# Isolated_gate_drive.net
KiCad netlist of a schematic drawn in Altium Designer
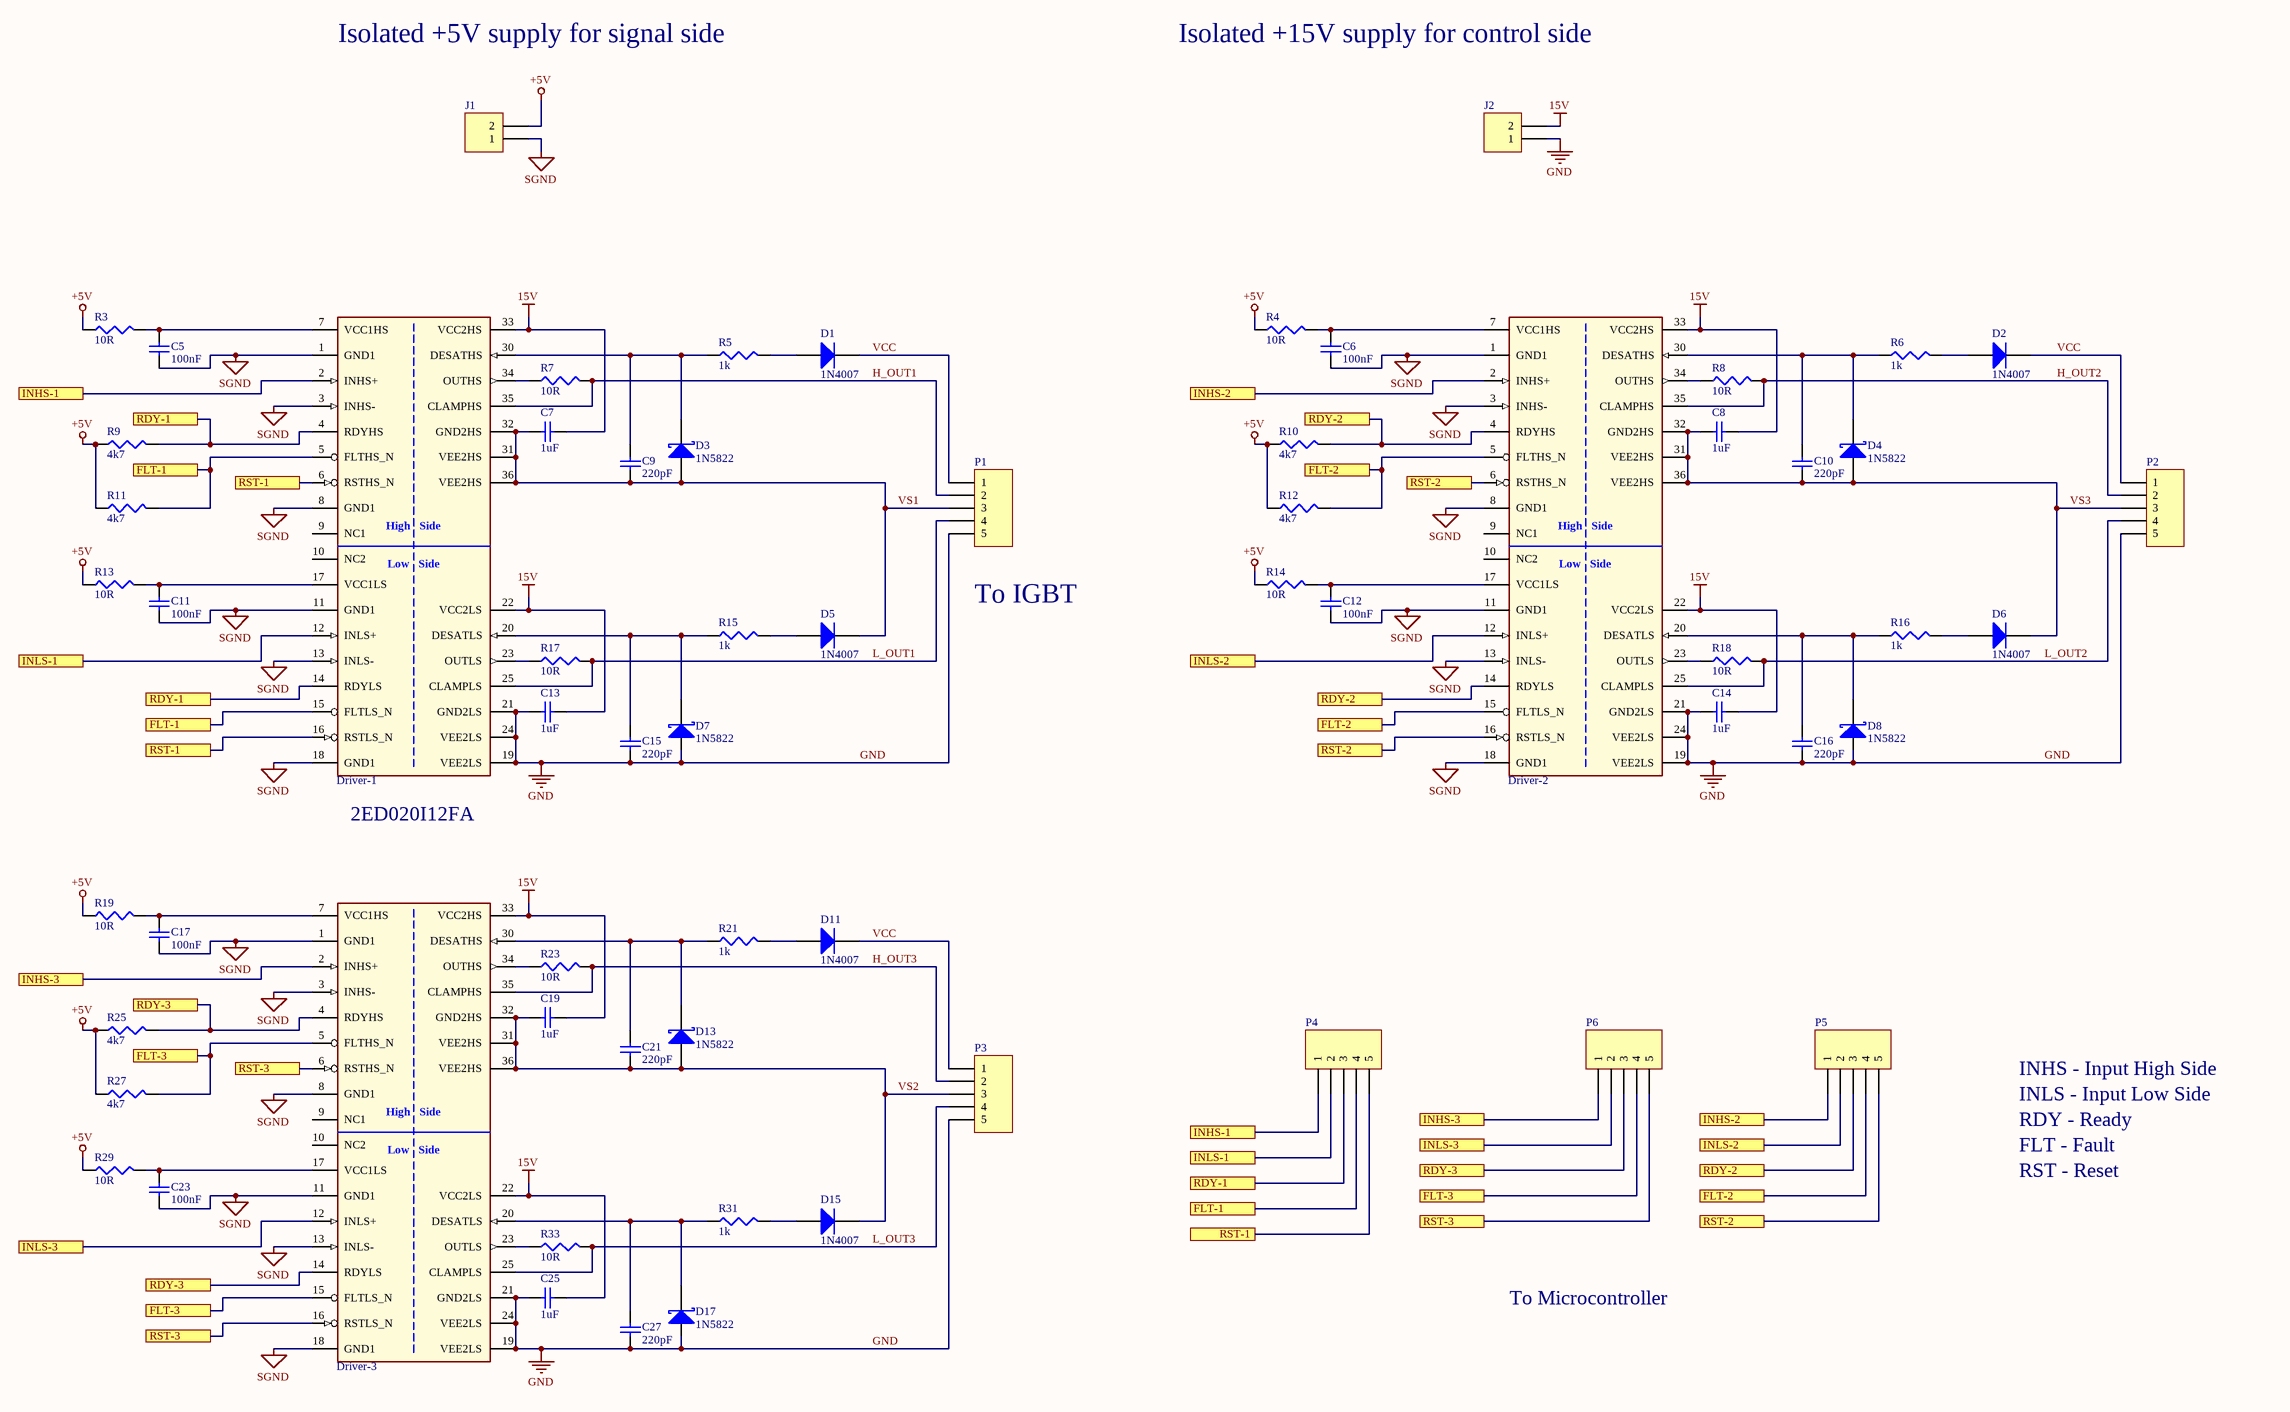
[diagram p0: Isolated_gate_drive.SchDoc]

(export (version "E")
  (design (tool "Eeschema 10.0.6"))
  (components
    (comp (ref "C5")
      (value "100nF")
      (footprint "C0805")
      (description "Capacitor")
      (fields (field (name "Comment") "Cap") (field (name "PUBLISHER") "Altium Limited"))
      (libsource (lib "Miscellaneous Devices") (part "Cap"))
    )
    (comp (ref "C6")
      (value "100nF")
      (footprint "C0805")
      (description "Capacitor")
      (fields (field (name "Comment") "Cap") (field (name "PUBLISHER") "Altium Limited"))
      (libsource (lib "Miscellaneous Devices") (part "Cap"))
    )
    (comp (ref "C7")
      (value "1uF")
      (footprint "C0805")
      (description "Capacitor")
      (fields (field (name "Comment") "Cap") (field (name "PUBLISHER") "Altium Limited"))
      (libsource (lib "Miscellaneous Devices") (part "Cap"))
    )
    (comp (ref "C8")
      (value "1uF")
      (footprint "C0805")
      (description "Capacitor")
      (fields (field (name "Comment") "Cap") (field (name "PUBLISHER") "Altium Limited"))
      (libsource (lib "Miscellaneous Devices") (part "Cap"))
    )
    (comp (ref "C9")
      (value "220pF")
      (footprint "C0805")
      (description "Capacitor")
      (fields (field (name "Comment") "Cap") (field (name "PUBLISHER") "Altium Limited"))
      (libsource (lib "Miscellaneous Devices") (part "Cap"))
    )
    (comp (ref "C10")
      (value "220pF")
      (footprint "C0805")
      (description "Capacitor")
      (fields (field (name "Comment") "Cap") (field (name "PUBLISHER") "Altium Limited"))
      (libsource (lib "Miscellaneous Devices") (part "Cap"))
    )
    (comp (ref "C11")
      (value "100nF")
      (footprint "C0805")
      (description "Capacitor")
      (fields (field (name "Comment") "Cap") (field (name "PUBLISHER") "Altium Limited"))
      (libsource (lib "Miscellaneous Devices") (part "Cap"))
    )
    (comp (ref "C12")
      (value "100nF")
      (footprint "C0805")
      (description "Capacitor")
      (fields (field (name "Comment") "Cap") (field (name "PUBLISHER") "Altium Limited"))
      (libsource (lib "Miscellaneous Devices") (part "Cap"))
    )
    (comp (ref "C13")
      (value "1uF")
      (footprint "C0805")
      (description "Capacitor")
      (fields (field (name "Comment") "Cap") (field (name "PUBLISHER") "Altium Limited"))
      (libsource (lib "Miscellaneous Devices") (part "Cap"))
    )
    (comp (ref "C14")
      (value "1uF")
      (footprint "C0805")
      (description "Capacitor")
      (fields (field (name "Comment") "Cap") (field (name "PUBLISHER") "Altium Limited"))
      (libsource (lib "Miscellaneous Devices") (part "Cap"))
    )
    (comp (ref "C15")
      (value "220pF")
      (footprint "C0805")
      (description "Capacitor")
      (fields (field (name "Comment") "Cap") (field (name "PUBLISHER") "Altium Limited"))
      (libsource (lib "Miscellaneous Devices") (part "Cap"))
    )
    (comp (ref "C16")
      (value "220pF")
      (footprint "C0805")
      (description "Capacitor")
      (fields (field (name "Comment") "Cap") (field (name "PUBLISHER") "Altium Limited"))
      (libsource (lib "Miscellaneous Devices") (part "Cap"))
    )
    (comp (ref "C17")
      (value "100nF")
      (footprint "C0805")
      (description "Capacitor")
      (fields (field (name "Comment") "Cap") (field (name "PUBLISHER") "Altium Limited"))
      (libsource (lib "Miscellaneous Devices") (part "Cap"))
    )
    (comp (ref "C19")
      (value "1uF")
      (footprint "C0805")
      (description "Capacitor")
      (fields (field (name "Comment") "Cap") (field (name "PUBLISHER") "Altium Limited"))
      (libsource (lib "Miscellaneous Devices") (part "Cap"))
    )
    (comp (ref "C21")
      (value "220pF")
      (footprint "C0805")
      (description "Capacitor")
      (fields (field (name "Comment") "Cap") (field (name "PUBLISHER") "Altium Limited"))
      (libsource (lib "Miscellaneous Devices") (part "Cap"))
    )
    (comp (ref "C23")
      (value "100nF")
      (footprint "C0805")
      (description "Capacitor")
      (fields (field (name "Comment") "Cap") (field (name "PUBLISHER") "Altium Limited"))
      (libsource (lib "Miscellaneous Devices") (part "Cap"))
    )
    (comp (ref "C25")
      (value "1uF")
      (footprint "C0805")
      (description "Capacitor")
      (fields (field (name "Comment") "Cap") (field (name "PUBLISHER") "Altium Limited"))
      (libsource (lib "Miscellaneous Devices") (part "Cap"))
    )
    (comp (ref "C27")
      (value "220pF")
      (footprint "C0805")
      (description "Capacitor")
      (fields (field (name "Comment") "Cap") (field (name "PUBLISHER") "Altium Limited"))
      (libsource (lib "Miscellaneous Devices") (part "Cap"))
    )
    (comp (ref "D1")
      (value "1N4007")
      (footprint "M7 SMA")
      (description "Default Diode")
      (fields (field (name "PUBLISHER") "Altium Limited"))
      (libsource (lib "Miscellaneous Devices") (part "Diode"))
    )
    (comp (ref "D2")
      (value "1N4007")
      (footprint "M7 SMA")
      (description "Default Diode")
      (fields (field (name "PUBLISHER") "Altium Limited"))
      (libsource (lib "Miscellaneous Devices") (part "Diode"))
    )
    (comp (ref "D3")
      (value "1N5822")
      (footprint "SMB")
      (description "Schottky Diode")
      (fields (field (name "PUBLISHER") "Altium Limited"))
      (libsource (lib "Miscellaneous Devices") (part "D Schottky"))
    )
    (comp (ref "D4")
      (value "1N5822")
      (footprint "SMB")
      (description "Schottky Diode")
      (fields (field (name "PUBLISHER") "Altium Limited"))
      (libsource (lib "Miscellaneous Devices") (part "D Schottky"))
    )
    (comp (ref "D5")
      (value "1N4007")
      (footprint "M7 SMA")
      (description "Default Diode")
      (fields (field (name "PUBLISHER") "Altium Limited"))
      (libsource (lib "Miscellaneous Devices") (part "Diode"))
    )
    (comp (ref "D6")
      (value "1N4007")
      (footprint "M7 SMA")
      (description "Default Diode")
      (fields (field (name "PUBLISHER") "Altium Limited"))
      (libsource (lib "Miscellaneous Devices") (part "Diode"))
    )
    (comp (ref "D7")
      (value "1N5822")
      (footprint "SMB")
      (description "Schottky Diode")
      (fields (field (name "PUBLISHER") "Altium Limited"))
      (libsource (lib "Miscellaneous Devices") (part "D Schottky"))
    )
    (comp (ref "D8")
      (value "1N5822")
      (footprint "SMB")
      (description "Schottky Diode")
      (fields (field (name "PUBLISHER") "Altium Limited"))
      (libsource (lib "Miscellaneous Devices") (part "D Schottky"))
    )
    (comp (ref "D11")
      (value "1N4007")
      (footprint "M7 SMA")
      (description "Default Diode")
      (fields (field (name "PUBLISHER") "Altium Limited"))
      (libsource (lib "Miscellaneous Devices") (part "Diode"))
    )
    (comp (ref "D13")
      (value "1N5822")
      (footprint "SMB")
      (description "Schottky Diode")
      (fields (field (name "PUBLISHER") "Altium Limited"))
      (libsource (lib "Miscellaneous Devices") (part "D Schottky"))
    )
    (comp (ref "D15")
      (value "1N4007")
      (footprint "M7 SMA")
      (description "Default Diode")
      (fields (field (name "PUBLISHER") "Altium Limited"))
      (libsource (lib "Miscellaneous Devices") (part "Diode"))
    )
    (comp (ref "D17")
      (value "1N5822")
      (footprint "SMB")
      (description "Schottky Diode")
      (fields (field (name "PUBLISHER") "Altium Limited"))
      (libsource (lib "Miscellaneous Devices") (part "D Schottky"))
    )
    (comp (ref "Driver-1")
      (value "2ED020I12FA")
      (footprint "SOP65P1030X265-36_32N-V:SOP65P1030X265-36_32N-V")
      (description "Dual IGBT Driver IC")
      (fields (field (name "MANUFACTURER") "Infineon Technologies"))
      (libsource (lib "2ED020I12FA") (part "2ED020I12FA"))
    )
    (comp (ref "Driver-2")
      (value "2ED020I12FA")
      (footprint "SOP65P1030X265-36_32N-V:SOP65P1030X265-36_32N-V")
      (description "Dual IGBT Driver IC")
      (fields (field (name "MANUFACTURER") "Infineon Technologies"))
      (libsource (lib "2ED020I12FA") (part "2ED020I12FA"))
    )
    (comp (ref "Driver-3")
      (value "2ED020I12FA")
      (footprint "SOP65P1030X265-36_32N-V:SOP65P1030X265-36_32N-V")
      (description "Dual IGBT Driver IC")
      (fields (field (name "MANUFACTURER") "Infineon Technologies"))
      (libsource (lib "2ED020I12FA") (part "2ED020I12FA"))
    )
    (comp (ref "J1")
      (value "Header 2")
      (footprint "HDR1X2")
      (description "Header, 2-Pin")
      (fields (field (name "PUBLISHER") "Altium Limited"))
      (libsource (lib "Miscellaneous Connectors") (part "Header 2"))
    )
    (comp (ref "J2")
      (value "Header 2")
      (footprint "HDR1X2")
      (description "Header, 2-Pin")
      (fields (field (name "PUBLISHER") "Altium Limited"))
      (libsource (lib "Miscellaneous Connectors") (part "Header 2"))
    )
    (comp (ref "P1")
      (value "Header 5")
      (footprint "HDR1X5")
      (description "Header, 5-Pin")
      (fields (field (name "PUBLISHER") "Altium Limited"))
      (libsource (lib "") (part "Header 5_1"))
    )
    (comp (ref "P2")
      (value "Header 5")
      (footprint "HDR1X5")
      (description "Header, 5-Pin")
      (fields (field (name "PUBLISHER") "Altium Limited"))
      (libsource (lib "") (part "Header 5_1"))
    )
    (comp (ref "P3")
      (value "Header 5")
      (footprint "HDR1X5")
      (description "Header, 5-Pin")
      (fields (field (name "PUBLISHER") "Altium Limited"))
      (libsource (lib "") (part "Header 5_1"))
    )
    (comp (ref "P4")
      (value "Header 5")
      (footprint "HDR1X5")
      (description "Header, 5-Pin")
      (fields (field (name "PUBLISHER") "Altium Limited"))
      (libsource (lib "Miscellaneous Connectors") (part "Header 5"))
    )
    (comp (ref "P5")
      (value "Header 5")
      (footprint "HDR1X5")
      (description "Header, 5-Pin")
      (fields (field (name "PUBLISHER") "Altium Limited"))
      (libsource (lib "Miscellaneous Connectors") (part "Header 5"))
    )
    (comp (ref "P6")
      (value "Header 5")
      (footprint "HDR1X5")
      (description "Header, 5-Pin")
      (fields (field (name "PUBLISHER") "Altium Limited"))
      (libsource (lib "Miscellaneous Connectors") (part "Header 5"))
    )
    (comp (ref "R3")
      (value "10R")
      (footprint "C1206")
      (description "Resistor")
      (fields (field (name "Comment") "Res3") (field (name "PUBLISHER") "Altium Limited"))
      (libsource (lib "Miscellaneous Devices") (part "Res3"))
    )
    (comp (ref "R4")
      (value "10R")
      (footprint "C1206")
      (description "Resistor")
      (fields (field (name "Comment") "Res3") (field (name "PUBLISHER") "Altium Limited"))
      (libsource (lib "Miscellaneous Devices") (part "Res3"))
    )
    (comp (ref "R5")
      (value "1k")
      (footprint "C1206")
      (description "Resistor")
      (fields (field (name "Comment") "Res3") (field (name "PUBLISHER") "Altium Limited"))
      (libsource (lib "Miscellaneous Devices") (part "Res3"))
    )
    (comp (ref "R6")
      (value "1k")
      (footprint "C1206")
      (description "Resistor")
      (fields (field (name "Comment") "Res3") (field (name "PUBLISHER") "Altium Limited"))
      (libsource (lib "Miscellaneous Devices") (part "Res3"))
    )
    (comp (ref "R7")
      (value "10R")
      (footprint "C1206")
      (description "Resistor")
      (fields (field (name "Comment") "Res3") (field (name "PUBLISHER") "Altium Limited"))
      (libsource (lib "Miscellaneous Devices") (part "Res3"))
    )
    (comp (ref "R8")
      (value "10R")
      (footprint "C1206")
      (description "Resistor")
      (fields (field (name "Comment") "Res3") (field (name "PUBLISHER") "Altium Limited"))
      (libsource (lib "Miscellaneous Devices") (part "Res3"))
    )
    (comp (ref "R9")
      (value "4k7")
      (footprint "C1206")
      (description "Resistor")
      (fields (field (name "Comment") "Res3") (field (name "PUBLISHER") "Altium Limited"))
      (libsource (lib "Miscellaneous Devices") (part "Res3"))
    )
    (comp (ref "R10")
      (value "4k7")
      (footprint "C1206")
      (description "Resistor")
      (fields (field (name "Comment") "Res3") (field (name "PUBLISHER") "Altium Limited"))
      (libsource (lib "Miscellaneous Devices") (part "Res3"))
    )
    (comp (ref "R11")
      (value "4k7")
      (footprint "C1206")
      (description "Resistor")
      (fields (field (name "Comment") "Res3") (field (name "PUBLISHER") "Altium Limited"))
      (libsource (lib "Miscellaneous Devices") (part "Res3"))
    )
    (comp (ref "R12")
      (value "4k7")
      (footprint "C1206")
      (description "Resistor")
      (fields (field (name "Comment") "Res3") (field (name "PUBLISHER") "Altium Limited"))
      (libsource (lib "Miscellaneous Devices") (part "Res3"))
    )
    (comp (ref "R13")
      (value "10R")
      (footprint "C1206")
      (description "Resistor")
      (fields (field (name "Comment") "Res3") (field (name "PUBLISHER") "Altium Limited"))
      (libsource (lib "Miscellaneous Devices") (part "Res3"))
    )
    (comp (ref "R14")
      (value "10R")
      (footprint "C1206")
      (description "Resistor")
      (fields (field (name "Comment") "Res3") (field (name "PUBLISHER") "Altium Limited"))
      (libsource (lib "Miscellaneous Devices") (part "Res3"))
    )
    (comp (ref "R15")
      (value "1k")
      (footprint "C1206")
      (description "Resistor")
      (fields (field (name "Comment") "Res3") (field (name "PUBLISHER") "Altium Limited"))
      (libsource (lib "Miscellaneous Devices") (part "Res3"))
    )
    (comp (ref "R16")
      (value "1k")
      (footprint "C1206")
      (description "Resistor")
      (fields (field (name "Comment") "Res3") (field (name "PUBLISHER") "Altium Limited"))
      (libsource (lib "Miscellaneous Devices") (part "Res3"))
    )
    (comp (ref "R17")
      (value "10R")
      (footprint "C1206")
      (description "Resistor")
      (fields (field (name "Comment") "Res3") (field (name "PUBLISHER") "Altium Limited"))
      (libsource (lib "Miscellaneous Devices") (part "Res3"))
    )
    (comp (ref "R18")
      (value "10R")
      (footprint "C1206")
      (description "Resistor")
      (fields (field (name "Comment") "Res3") (field (name "PUBLISHER") "Altium Limited"))
      (libsource (lib "Miscellaneous Devices") (part "Res3"))
    )
    (comp (ref "R19")
      (value "10R")
      (footprint "C1206")
      (description "Resistor")
      (fields (field (name "Comment") "Res3") (field (name "PUBLISHER") "Altium Limited"))
      (libsource (lib "Miscellaneous Devices") (part "Res3"))
    )
    (comp (ref "R21")
      (value "1k")
      (footprint "C1206")
      (description "Resistor")
      (fields (field (name "Comment") "Res3") (field (name "PUBLISHER") "Altium Limited"))
      (libsource (lib "Miscellaneous Devices") (part "Res3"))
    )
    (comp (ref "R23")
      (value "10R")
      (footprint "C1206")
      (description "Resistor")
      (fields (field (name "Comment") "Res3") (field (name "PUBLISHER") "Altium Limited"))
      (libsource (lib "Miscellaneous Devices") (part "Res3"))
    )
    (comp (ref "R25")
      (value "4k7")
      (footprint "C1206")
      (description "Resistor")
      (fields (field (name "Comment") "Res3") (field (name "PUBLISHER") "Altium Limited"))
      (libsource (lib "Miscellaneous Devices") (part "Res3"))
    )
    (comp (ref "R27")
      (value "4k7")
      (footprint "C1206")
      (description "Resistor")
      (fields (field (name "Comment") "Res3") (field (name "PUBLISHER") "Altium Limited"))
      (libsource (lib "Miscellaneous Devices") (part "Res3"))
    )
    (comp (ref "R29")
      (value "10R")
      (footprint "C1206")
      (description "Resistor")
      (fields (field (name "Comment") "Res3") (field (name "PUBLISHER") "Altium Limited"))
      (libsource (lib "Miscellaneous Devices") (part "Res3"))
    )
    (comp (ref "R31")
      (value "1k")
      (footprint "C1206")
      (description "Resistor")
      (fields (field (name "Comment") "Res3") (field (name "PUBLISHER") "Altium Limited"))
      (libsource (lib "Miscellaneous Devices") (part "Res3"))
    )
    (comp (ref "R33")
      (value "10R")
      (footprint "C1206")
      (description "Resistor")
      (fields (field (name "Comment") "Res3") (field (name "PUBLISHER") "Altium Limited"))
      (libsource (lib "Miscellaneous Devices") (part "Res3"))
    )
  )
  (nets
    (net (code "1") (name "+5V") (class "Default")
      (node (ref "J1") (pin "2") (pinfunction "2_2") (pintype "passive"))
      (node (ref "R10") (pin "1") (pinfunction "1_1") (pintype "passive"))
      (node (ref "R11") (pin "1") (pinfunction "1_1") (pintype "passive"))
      (node (ref "R12") (pin "1") (pinfunction "1_1") (pintype "passive"))
      (node (ref "R13") (pin "1") (pinfunction "1_1") (pintype "passive"))
      (node (ref "R14") (pin "1") (pinfunction "1_1") (pintype "passive"))
      (node (ref "R19") (pin "1") (pinfunction "1_1") (pintype "passive"))
      (node (ref "R25") (pin "1") (pinfunction "1_1") (pintype "passive"))
      (node (ref "R27") (pin "1") (pinfunction "1_1") (pintype "passive"))
      (node (ref "R29") (pin "1") (pinfunction "1_1") (pintype "passive"))
      (node (ref "R3") (pin "1") (pinfunction "1_1") (pintype "passive"))
      (node (ref "R4") (pin "1") (pinfunction "1_1") (pintype "passive"))
      (node (ref "R9") (pin "1") (pinfunction "1_1") (pintype "passive"))
    )
    (net (code "2") (name "/FLT-1") (class "Default")
      (node (ref "Driver-1") (pin "15") (pinfunction "FLTLS_N_15") (pintype "open_collector"))
      (node (ref "Driver-1") (pin "5") (pinfunction "FLTHS_N_5") (pintype "open_collector"))
      (node (ref "P4") (pin "4") (pinfunction "4_4") (pintype "passive"))
      (node (ref "R11") (pin "2") (pinfunction "2_2") (pintype "passive"))
    )
    (net (code "3") (name "/FLT-2") (class "Default")
      (node (ref "Driver-2") (pin "15") (pinfunction "FLTLS_N_15") (pintype "open_collector"))
      (node (ref "Driver-2") (pin "5") (pinfunction "FLTHS_N_5") (pintype "open_collector"))
      (node (ref "P5") (pin "4") (pinfunction "4_4") (pintype "passive"))
      (node (ref "R12") (pin "2") (pinfunction "2_2") (pintype "passive"))
    )
    (net (code "4") (name "/FLT-3") (class "Default")
      (node (ref "Driver-3") (pin "15") (pinfunction "FLTLS_N_15") (pintype "open_collector"))
      (node (ref "Driver-3") (pin "5") (pinfunction "FLTHS_N_5") (pintype "open_collector"))
      (node (ref "P6") (pin "4") (pinfunction "4_4") (pintype "passive"))
      (node (ref "R27") (pin "2") (pinfunction "2_2") (pintype "passive"))
    )
    (net (code "5") (name "/H_OUT1") (class "Default")
      (node (ref "Driver-1") (pin "35") (pinfunction "CLAMPHS_35") (pintype "passive"))
      (node (ref "P1") (pin "2") (pinfunction "2_2") (pintype "passive"))
      (node (ref "R7") (pin "2") (pinfunction "2_2") (pintype "passive"))
    )
    (net (code "6") (name "/H_OUT2") (class "Default")
      (node (ref "Driver-2") (pin "35") (pinfunction "CLAMPHS_35") (pintype "passive"))
      (node (ref "P2") (pin "2") (pinfunction "2_2") (pintype "passive"))
      (node (ref "R8") (pin "2") (pinfunction "2_2") (pintype "passive"))
    )
    (net (code "7") (name "/H_OUT3") (class "Default")
      (node (ref "Driver-3") (pin "35") (pinfunction "CLAMPHS_35") (pintype "passive"))
      (node (ref "P3") (pin "2") (pinfunction "2_2") (pintype "passive"))
      (node (ref "R23") (pin "2") (pinfunction "2_2") (pintype "passive"))
    )
    (net (code "8") (name "/INHS-1") (class "Default")
      (node (ref "Driver-1") (pin "2") (pinfunction "INHS+_2") (pintype "input"))
      (node (ref "P4") (pin "1") (pinfunction "1_1") (pintype "passive"))
    )
    (net (code "9") (name "/INHS-2") (class "Default")
      (node (ref "Driver-2") (pin "2") (pinfunction "INHS+_2") (pintype "input"))
      (node (ref "P5") (pin "1") (pinfunction "1_1") (pintype "passive"))
    )
    (net (code "10") (name "/INHS-3") (class "Default")
      (node (ref "Driver-3") (pin "2") (pinfunction "INHS+_2") (pintype "input"))
      (node (ref "P6") (pin "1") (pinfunction "1_1") (pintype "passive"))
    )
    (net (code "11") (name "/INLS-1") (class "Default")
      (node (ref "Driver-1") (pin "12") (pinfunction "INLS+_12") (pintype "input"))
      (node (ref "P4") (pin "2") (pinfunction "2_2") (pintype "passive"))
    )
    (net (code "12") (name "/INLS-2") (class "Default")
      (node (ref "Driver-2") (pin "12") (pinfunction "INLS+_12") (pintype "input"))
      (node (ref "P5") (pin "2") (pinfunction "2_2") (pintype "passive"))
    )
    (net (code "13") (name "/INLS-3") (class "Default")
      (node (ref "Driver-3") (pin "12") (pinfunction "INLS+_12") (pintype "input"))
      (node (ref "P6") (pin "2") (pinfunction "2_2") (pintype "passive"))
    )
    (net (code "14") (name "/L_OUT1") (class "Default")
      (node (ref "Driver-1") (pin "25") (pinfunction "CLAMPLS_25") (pintype "passive"))
      (node (ref "P1") (pin "4") (pinfunction "4_4") (pintype "passive"))
      (node (ref "R17") (pin "2") (pinfunction "2_2") (pintype "passive"))
    )
    (net (code "15") (name "/L_OUT2") (class "Default")
      (node (ref "Driver-2") (pin "25") (pinfunction "CLAMPLS_25") (pintype "passive"))
      (node (ref "P2") (pin "4") (pinfunction "4_4") (pintype "passive"))
      (node (ref "R18") (pin "2") (pinfunction "2_2") (pintype "passive"))
    )
    (net (code "16") (name "/L_OUT3") (class "Default")
      (node (ref "Driver-3") (pin "25") (pinfunction "CLAMPLS_25") (pintype "passive"))
      (node (ref "P3") (pin "4") (pinfunction "4_4") (pintype "passive"))
      (node (ref "R33") (pin "2") (pinfunction "2_2") (pintype "passive"))
    )
    (net (code "17") (name "/RDY-1") (class "Default")
      (node (ref "Driver-1") (pin "14") (pinfunction "RDYLS_14") (pintype "open_collector"))
      (node (ref "Driver-1") (pin "4") (pinfunction "RDYHS_4") (pintype "open_collector"))
      (node (ref "P4") (pin "3") (pinfunction "3_3") (pintype "passive"))
      (node (ref "R9") (pin "2") (pinfunction "2_2") (pintype "passive"))
    )
    (net (code "18") (name "/RDY-2") (class "Default")
      (node (ref "Driver-2") (pin "14") (pinfunction "RDYLS_14") (pintype "open_collector"))
      (node (ref "Driver-2") (pin "4") (pinfunction "RDYHS_4") (pintype "open_collector"))
      (node (ref "P5") (pin "3") (pinfunction "3_3") (pintype "passive"))
      (node (ref "R10") (pin "2") (pinfunction "2_2") (pintype "passive"))
    )
    (net (code "19") (name "/RDY-3") (class "Default")
      (node (ref "Driver-3") (pin "14") (pinfunction "RDYLS_14") (pintype "open_collector"))
      (node (ref "Driver-3") (pin "4") (pinfunction "RDYHS_4") (pintype "open_collector"))
      (node (ref "P6") (pin "3") (pinfunction "3_3") (pintype "passive"))
      (node (ref "R25") (pin "2") (pinfunction "2_2") (pintype "passive"))
    )
    (net (code "20") (name "/RST-1") (class "Default")
      (node (ref "Driver-1") (pin "16") (pinfunction "RSTLS_N_16") (pintype "input"))
      (node (ref "Driver-1") (pin "6") (pinfunction "RSTHS_N_6") (pintype "input"))
      (node (ref "P4") (pin "5") (pinfunction "5_5") (pintype "passive"))
    )
    (net (code "21") (name "/RST-2") (class "Default")
      (node (ref "Driver-2") (pin "16") (pinfunction "RSTLS_N_16") (pintype "input"))
      (node (ref "Driver-2") (pin "6") (pinfunction "RSTHS_N_6") (pintype "input"))
      (node (ref "P5") (pin "5") (pinfunction "5_5") (pintype "passive"))
    )
    (net (code "22") (name "/RST-3") (class "Default")
      (node (ref "Driver-3") (pin "16") (pinfunction "RSTLS_N_16") (pintype "input"))
      (node (ref "Driver-3") (pin "6") (pinfunction "RSTHS_N_6") (pintype "input"))
      (node (ref "P6") (pin "5") (pinfunction "5_5") (pintype "passive"))
    )
    (net (code "23") (name "/VCC") (class "Default")
      (node (ref "D1") (pin "2") (pinfunction "K_2") (pintype "passive"))
      (node (ref "D11") (pin "2") (pinfunction "K_2") (pintype "passive"))
      (node (ref "D2") (pin "2") (pinfunction "K_2") (pintype "passive"))
      (node (ref "P1") (pin "1") (pinfunction "1_1") (pintype "passive"))
      (node (ref "P2") (pin "1") (pinfunction "1_1") (pintype "passive"))
      (node (ref "P3") (pin "1") (pinfunction "1_1") (pintype "passive"))
    )
    (net (code "24") (name "/VS1") (class "Default")
      (node (ref "C7") (pin "1") (pinfunction "1_1") (pintype "passive"))
      (node (ref "C9") (pin "2") (pinfunction "2_2") (pintype "passive"))
      (node (ref "D3") (pin "1") (pinfunction "A_1") (pintype "passive"))
      (node (ref "D5") (pin "2") (pinfunction "K_2") (pintype "passive"))
      (node (ref "Driver-1") (pin "31") (pinfunction "VEE2HS_31") (pintype "power_in"))
      (node (ref "Driver-1") (pin "32") (pinfunction "GND2HS_32") (pintype "power_in"))
      (node (ref "Driver-1") (pin "36") (pinfunction "VEE2HS_36") (pintype "power_in"))
      (node (ref "P1") (pin "3") (pinfunction "3_3") (pintype "passive"))
    )
    (net (code "25") (name "/VS2") (class "Default")
      (node (ref "C19") (pin "1") (pinfunction "1_1") (pintype "passive"))
      (node (ref "C21") (pin "2") (pinfunction "2_2") (pintype "passive"))
      (node (ref "D13") (pin "1") (pinfunction "A_1") (pintype "passive"))
      (node (ref "D15") (pin "2") (pinfunction "K_2") (pintype "passive"))
      (node (ref "Driver-3") (pin "31") (pinfunction "VEE2HS_31") (pintype "power_in"))
      (node (ref "Driver-3") (pin "32") (pinfunction "GND2HS_32") (pintype "power_in"))
      (node (ref "Driver-3") (pin "36") (pinfunction "VEE2HS_36") (pintype "power_in"))
      (node (ref "P3") (pin "3") (pinfunction "3_3") (pintype "passive"))
    )
    (net (code "26") (name "/VS3") (class "Default")
      (node (ref "C10") (pin "2") (pinfunction "2_2") (pintype "passive"))
      (node (ref "C8") (pin "1") (pinfunction "1_1") (pintype "passive"))
      (node (ref "D4") (pin "1") (pinfunction "A_1") (pintype "passive"))
      (node (ref "D6") (pin "2") (pinfunction "K_2") (pintype "passive"))
      (node (ref "Driver-2") (pin "31") (pinfunction "VEE2HS_31") (pintype "power_in"))
      (node (ref "Driver-2") (pin "32") (pinfunction "GND2HS_32") (pintype "power_in"))
      (node (ref "Driver-2") (pin "36") (pinfunction "VEE2HS_36") (pintype "power_in"))
      (node (ref "P2") (pin "3") (pinfunction "3_3") (pintype "passive"))
    )
    (net (code "27") (name "15V") (class "Default")
      (node (ref "C13") (pin "2") (pinfunction "2_2") (pintype "passive"))
      (node (ref "C14") (pin "2") (pinfunction "2_2") (pintype "passive"))
      (node (ref "C19") (pin "2") (pinfunction "2_2") (pintype "passive"))
      (node (ref "C25") (pin "2") (pinfunction "2_2") (pintype "passive"))
      (node (ref "C7") (pin "2") (pinfunction "2_2") (pintype "passive"))
      (node (ref "C8") (pin "2") (pinfunction "2_2") (pintype "passive"))
      (node (ref "Driver-1") (pin "22") (pinfunction "VCC2LS_22") (pintype "power_in"))
      (node (ref "Driver-1") (pin "33") (pinfunction "VCC2HS_33") (pintype "power_in"))
      (node (ref "Driver-2") (pin "22") (pinfunction "VCC2LS_22") (pintype "power_in"))
      (node (ref "Driver-2") (pin "33") (pinfunction "VCC2HS_33") (pintype "power_in"))
      (node (ref "Driver-3") (pin "22") (pinfunction "VCC2LS_22") (pintype "power_in"))
      (node (ref "Driver-3") (pin "33") (pinfunction "VCC2HS_33") (pintype "power_in"))
      (node (ref "J2") (pin "2") (pinfunction "2_2") (pintype "passive"))
    )
    (net (code "28") (name "GND") (class "Default")
      (node (ref "C13") (pin "1") (pinfunction "1_1") (pintype "passive"))
      (node (ref "C14") (pin "1") (pinfunction "1_1") (pintype "passive"))
      (node (ref "C15") (pin "2") (pinfunction "2_2") (pintype "passive"))
      (node (ref "C16") (pin "2") (pinfunction "2_2") (pintype "passive"))
      (node (ref "C25") (pin "1") (pinfunction "1_1") (pintype "passive"))
      (node (ref "C27") (pin "2") (pinfunction "2_2") (pintype "passive"))
      (node (ref "D17") (pin "1") (pinfunction "A_1") (pintype "passive"))
      (node (ref "D7") (pin "1") (pinfunction "A_1") (pintype "passive"))
      (node (ref "D8") (pin "1") (pinfunction "A_1") (pintype "passive"))
      (node (ref "Driver-1") (pin "19") (pinfunction "VEE2LS_19") (pintype "power_in"))
      (node (ref "Driver-1") (pin "21") (pinfunction "GND2LS_21") (pintype "power_in"))
      (node (ref "Driver-1") (pin "24") (pinfunction "VEE2LS_24") (pintype "power_in"))
      (node (ref "Driver-2") (pin "19") (pinfunction "VEE2LS_19") (pintype "power_in"))
      (node (ref "Driver-2") (pin "21") (pinfunction "GND2LS_21") (pintype "power_in"))
      (node (ref "Driver-2") (pin "24") (pinfunction "VEE2LS_24") (pintype "power_in"))
      (node (ref "Driver-3") (pin "19") (pinfunction "VEE2LS_19") (pintype "power_in"))
      (node (ref "Driver-3") (pin "21") (pinfunction "GND2LS_21") (pintype "power_in"))
      (node (ref "Driver-3") (pin "24") (pinfunction "VEE2LS_24") (pintype "power_in"))
      (node (ref "J2") (pin "1") (pinfunction "1_1") (pintype "passive"))
      (node (ref "P1") (pin "5") (pinfunction "5_5") (pintype "passive"))
      (node (ref "P2") (pin "5") (pinfunction "5_5") (pintype "passive"))
      (node (ref "P3") (pin "5") (pinfunction "5_5") (pintype "passive"))
    )
    (net (code "29") (name "Net-(D1-A)") (class "Default")
      (node (ref "D1") (pin "1") (pinfunction "A_1") (pintype "passive"))
      (node (ref "R5") (pin "2") (pinfunction "2_2") (pintype "passive"))
    )
    (net (code "30") (name "Net-(D2-A)") (class "Default")
      (node (ref "D2") (pin "1") (pinfunction "A_1") (pintype "passive"))
      (node (ref "R6") (pin "2") (pinfunction "2_2") (pintype "passive"))
    )
    (net (code "31") (name "Net-(D3-K)") (class "Default")
      (node (ref "C9") (pin "1") (pinfunction "1_1") (pintype "passive"))
      (node (ref "D3") (pin "2") (pinfunction "K_2") (pintype "passive"))
      (node (ref "Driver-1") (pin "30") (pinfunction "DESATHS_30") (pintype "input"))
      (node (ref "R5") (pin "1") (pinfunction "1_1") (pintype "passive"))
    )
    (net (code "32") (name "Net-(D4-K)") (class "Default")
      (node (ref "C10") (pin "1") (pinfunction "1_1") (pintype "passive"))
      (node (ref "D4") (pin "2") (pinfunction "K_2") (pintype "passive"))
      (node (ref "Driver-2") (pin "30") (pinfunction "DESATHS_30") (pintype "input"))
      (node (ref "R6") (pin "1") (pinfunction "1_1") (pintype "passive"))
    )
    (net (code "33") (name "Net-(D5-A)") (class "Default")
      (node (ref "D5") (pin "1") (pinfunction "A_1") (pintype "passive"))
      (node (ref "R15") (pin "2") (pinfunction "2_2") (pintype "passive"))
    )
    (net (code "34") (name "Net-(D6-A)") (class "Default")
      (node (ref "D6") (pin "1") (pinfunction "A_1") (pintype "passive"))
      (node (ref "R16") (pin "2") (pinfunction "2_2") (pintype "passive"))
    )
    (net (code "35") (name "Net-(D7-K)") (class "Default")
      (node (ref "C15") (pin "1") (pinfunction "1_1") (pintype "passive"))
      (node (ref "D7") (pin "2") (pinfunction "K_2") (pintype "passive"))
      (node (ref "Driver-1") (pin "20") (pinfunction "DESATLS_20") (pintype "input"))
      (node (ref "R15") (pin "1") (pinfunction "1_1") (pintype "passive"))
    )
    (net (code "36") (name "Net-(D8-K)") (class "Default")
      (node (ref "C16") (pin "1") (pinfunction "1_1") (pintype "passive"))
      (node (ref "D8") (pin "2") (pinfunction "K_2") (pintype "passive"))
      (node (ref "Driver-2") (pin "20") (pinfunction "DESATLS_20") (pintype "input"))
      (node (ref "R16") (pin "1") (pinfunction "1_1") (pintype "passive"))
    )
    (net (code "37") (name "Net-(D11-A)") (class "Default")
      (node (ref "D11") (pin "1") (pinfunction "A_1") (pintype "passive"))
      (node (ref "R21") (pin "2") (pinfunction "2_2") (pintype "passive"))
    )
    (net (code "38") (name "Net-(D13-K)") (class "Default")
      (node (ref "C21") (pin "1") (pinfunction "1_1") (pintype "passive"))
      (node (ref "D13") (pin "2") (pinfunction "K_2") (pintype "passive"))
      (node (ref "Driver-3") (pin "30") (pinfunction "DESATHS_30") (pintype "input"))
      (node (ref "R21") (pin "1") (pinfunction "1_1") (pintype "passive"))
    )
    (net (code "39") (name "Net-(D15-A)") (class "Default")
      (node (ref "D15") (pin "1") (pinfunction "A_1") (pintype "passive"))
      (node (ref "R31") (pin "2") (pinfunction "2_2") (pintype "passive"))
    )
    (net (code "40") (name "Net-(D17-K)") (class "Default")
      (node (ref "C27") (pin "1") (pinfunction "1_1") (pintype "passive"))
      (node (ref "D17") (pin "2") (pinfunction "K_2") (pintype "passive"))
      (node (ref "Driver-3") (pin "20") (pinfunction "DESATLS_20") (pintype "input"))
      (node (ref "R31") (pin "1") (pinfunction "1_1") (pintype "passive"))
    )
    (net (code "41") (name "Net-(Driver-1-OUTHS)") (class "Default")
      (node (ref "Driver-1") (pin "34") (pinfunction "OUTHS_34") (pintype "output"))
      (node (ref "R7") (pin "1") (pinfunction "1_1") (pintype "passive"))
    )
    (net (code "42") (name "Net-(Driver-1-OUTLS)") (class "Default")
      (node (ref "Driver-1") (pin "23") (pinfunction "OUTLS_23") (pintype "output"))
      (node (ref "R17") (pin "1") (pinfunction "1_1") (pintype "passive"))
    )
    (net (code "43") (name "Net-(Driver-1-VCC1HS)") (class "Default")
      (node (ref "C5") (pin "1") (pinfunction "1_1") (pintype "passive"))
      (node (ref "Driver-1") (pin "7") (pinfunction "VCC1HS_7") (pintype "power_in"))
      (node (ref "R3") (pin "2") (pinfunction "2_2") (pintype "passive"))
    )
    (net (code "44") (name "Net-(Driver-1-VCC1LS)") (class "Default")
      (node (ref "C11") (pin "1") (pinfunction "1_1") (pintype "passive"))
      (node (ref "Driver-1") (pin "17") (pinfunction "VCC1LS_17") (pintype "power_in"))
      (node (ref "R13") (pin "2") (pinfunction "2_2") (pintype "passive"))
    )
    (net (code "45") (name "Net-(Driver-2-OUTHS)") (class "Default")
      (node (ref "Driver-2") (pin "34") (pinfunction "OUTHS_34") (pintype "output"))
      (node (ref "R8") (pin "1") (pinfunction "1_1") (pintype "passive"))
    )
    (net (code "46") (name "Net-(Driver-2-OUTLS)") (class "Default")
      (node (ref "Driver-2") (pin "23") (pinfunction "OUTLS_23") (pintype "output"))
      (node (ref "R18") (pin "1") (pinfunction "1_1") (pintype "passive"))
    )
    (net (code "47") (name "Net-(Driver-2-VCC1HS)") (class "Default")
      (node (ref "C6") (pin "1") (pinfunction "1_1") (pintype "passive"))
      (node (ref "Driver-2") (pin "7") (pinfunction "VCC1HS_7") (pintype "power_in"))
      (node (ref "R4") (pin "2") (pinfunction "2_2") (pintype "passive"))
    )
    (net (code "48") (name "Net-(Driver-2-VCC1LS)") (class "Default")
      (node (ref "C12") (pin "1") (pinfunction "1_1") (pintype "passive"))
      (node (ref "Driver-2") (pin "17") (pinfunction "VCC1LS_17") (pintype "power_in"))
      (node (ref "R14") (pin "2") (pinfunction "2_2") (pintype "passive"))
    )
    (net (code "49") (name "Net-(Driver-3-OUTHS)") (class "Default")
      (node (ref "Driver-3") (pin "34") (pinfunction "OUTHS_34") (pintype "output"))
      (node (ref "R23") (pin "1") (pinfunction "1_1") (pintype "passive"))
    )
    (net (code "50") (name "Net-(Driver-3-OUTLS)") (class "Default")
      (node (ref "Driver-3") (pin "23") (pinfunction "OUTLS_23") (pintype "output"))
      (node (ref "R33") (pin "1") (pinfunction "1_1") (pintype "passive"))
    )
    (net (code "51") (name "Net-(Driver-3-VCC1HS)") (class "Default")
      (node (ref "C17") (pin "1") (pinfunction "1_1") (pintype "passive"))
      (node (ref "Driver-3") (pin "7") (pinfunction "VCC1HS_7") (pintype "power_in"))
      (node (ref "R19") (pin "2") (pinfunction "2_2") (pintype "passive"))
    )
    (net (code "52") (name "Net-(Driver-3-VCC1LS)") (class "Default")
      (node (ref "C23") (pin "1") (pinfunction "1_1") (pintype "passive"))
      (node (ref "Driver-3") (pin "17") (pinfunction "VCC1LS_17") (pintype "power_in"))
      (node (ref "R29") (pin "2") (pinfunction "2_2") (pintype "passive"))
    )
    (net (code "53") (name "SGND") (class "Default")
      (node (ref "C11") (pin "2") (pinfunction "2_2") (pintype "passive"))
      (node (ref "C12") (pin "2") (pinfunction "2_2") (pintype "passive"))
      (node (ref "C17") (pin "2") (pinfunction "2_2") (pintype "passive"))
      (node (ref "C23") (pin "2") (pinfunction "2_2") (pintype "passive"))
      (node (ref "C5") (pin "2") (pinfunction "2_2") (pintype "passive"))
      (node (ref "C6") (pin "2") (pinfunction "2_2") (pintype "passive"))
      (node (ref "Driver-1") (pin "1") (pinfunction "GND1_1") (pintype "power_in"))
      (node (ref "Driver-1") (pin "11") (pinfunction "GND1_11") (pintype "power_in"))
      (node (ref "Driver-1") (pin "13") (pinfunction "INLS-_13") (pintype "input"))
      (node (ref "Driver-1") (pin "18") (pinfunction "GND1_18") (pintype "power_in"))
      (node (ref "Driver-1") (pin "3") (pinfunction "INHS-_3") (pintype "input"))
      (node (ref "Driver-1") (pin "8") (pinfunction "GND1_8") (pintype "power_in"))
      (node (ref "Driver-2") (pin "1") (pinfunction "GND1_1") (pintype "power_in"))
      (node (ref "Driver-2") (pin "11") (pinfunction "GND1_11") (pintype "power_in"))
      (node (ref "Driver-2") (pin "13") (pinfunction "INLS-_13") (pintype "input"))
      (node (ref "Driver-2") (pin "18") (pinfunction "GND1_18") (pintype "power_in"))
      (node (ref "Driver-2") (pin "3") (pinfunction "INHS-_3") (pintype "input"))
      (node (ref "Driver-2") (pin "8") (pinfunction "GND1_8") (pintype "power_in"))
      (node (ref "Driver-3") (pin "1") (pinfunction "GND1_1") (pintype "power_in"))
      (node (ref "Driver-3") (pin "11") (pinfunction "GND1_11") (pintype "power_in"))
      (node (ref "Driver-3") (pin "13") (pinfunction "INLS-_13") (pintype "input"))
      (node (ref "Driver-3") (pin "18") (pinfunction "GND1_18") (pintype "power_in"))
      (node (ref "Driver-3") (pin "3") (pinfunction "INHS-_3") (pintype "input"))
      (node (ref "Driver-3") (pin "8") (pinfunction "GND1_8") (pintype "power_in"))
      (node (ref "J1") (pin "1") (pinfunction "1_1") (pintype "passive"))
    )
    (net (code "54") (name "unconnected-(Driver-1-NC1-Pad9)") (class "Default")
      (node (ref "Driver-1") (pin "9") (pinfunction "NC1_9") (pintype "passive"))
    )
    (net (code "55") (name "unconnected-(Driver-1-NC2-Pad10)") (class "Default")
      (node (ref "Driver-1") (pin "10") (pinfunction "NC2_10") (pintype "passive"))
    )
    (net (code "56") (name "unconnected-(Driver-2-NC1-Pad9)") (class "Default")
      (node (ref "Driver-2") (pin "9") (pinfunction "NC1_9") (pintype "passive"))
    )
    (net (code "57") (name "unconnected-(Driver-2-NC2-Pad10)") (class "Default")
      (node (ref "Driver-2") (pin "10") (pinfunction "NC2_10") (pintype "passive"))
    )
    (net (code "58") (name "unconnected-(Driver-3-NC1-Pad9)") (class "Default")
      (node (ref "Driver-3") (pin "9") (pinfunction "NC1_9") (pintype "passive"))
    )
    (net (code "59") (name "unconnected-(Driver-3-NC2-Pad10)") (class "Default")
      (node (ref "Driver-3") (pin "10") (pinfunction "NC2_10") (pintype "passive"))
    )
  )
)
